# Trial_1_ECE411_Group_15.net
KiCad netlist of a schematic drawn in EAGLE
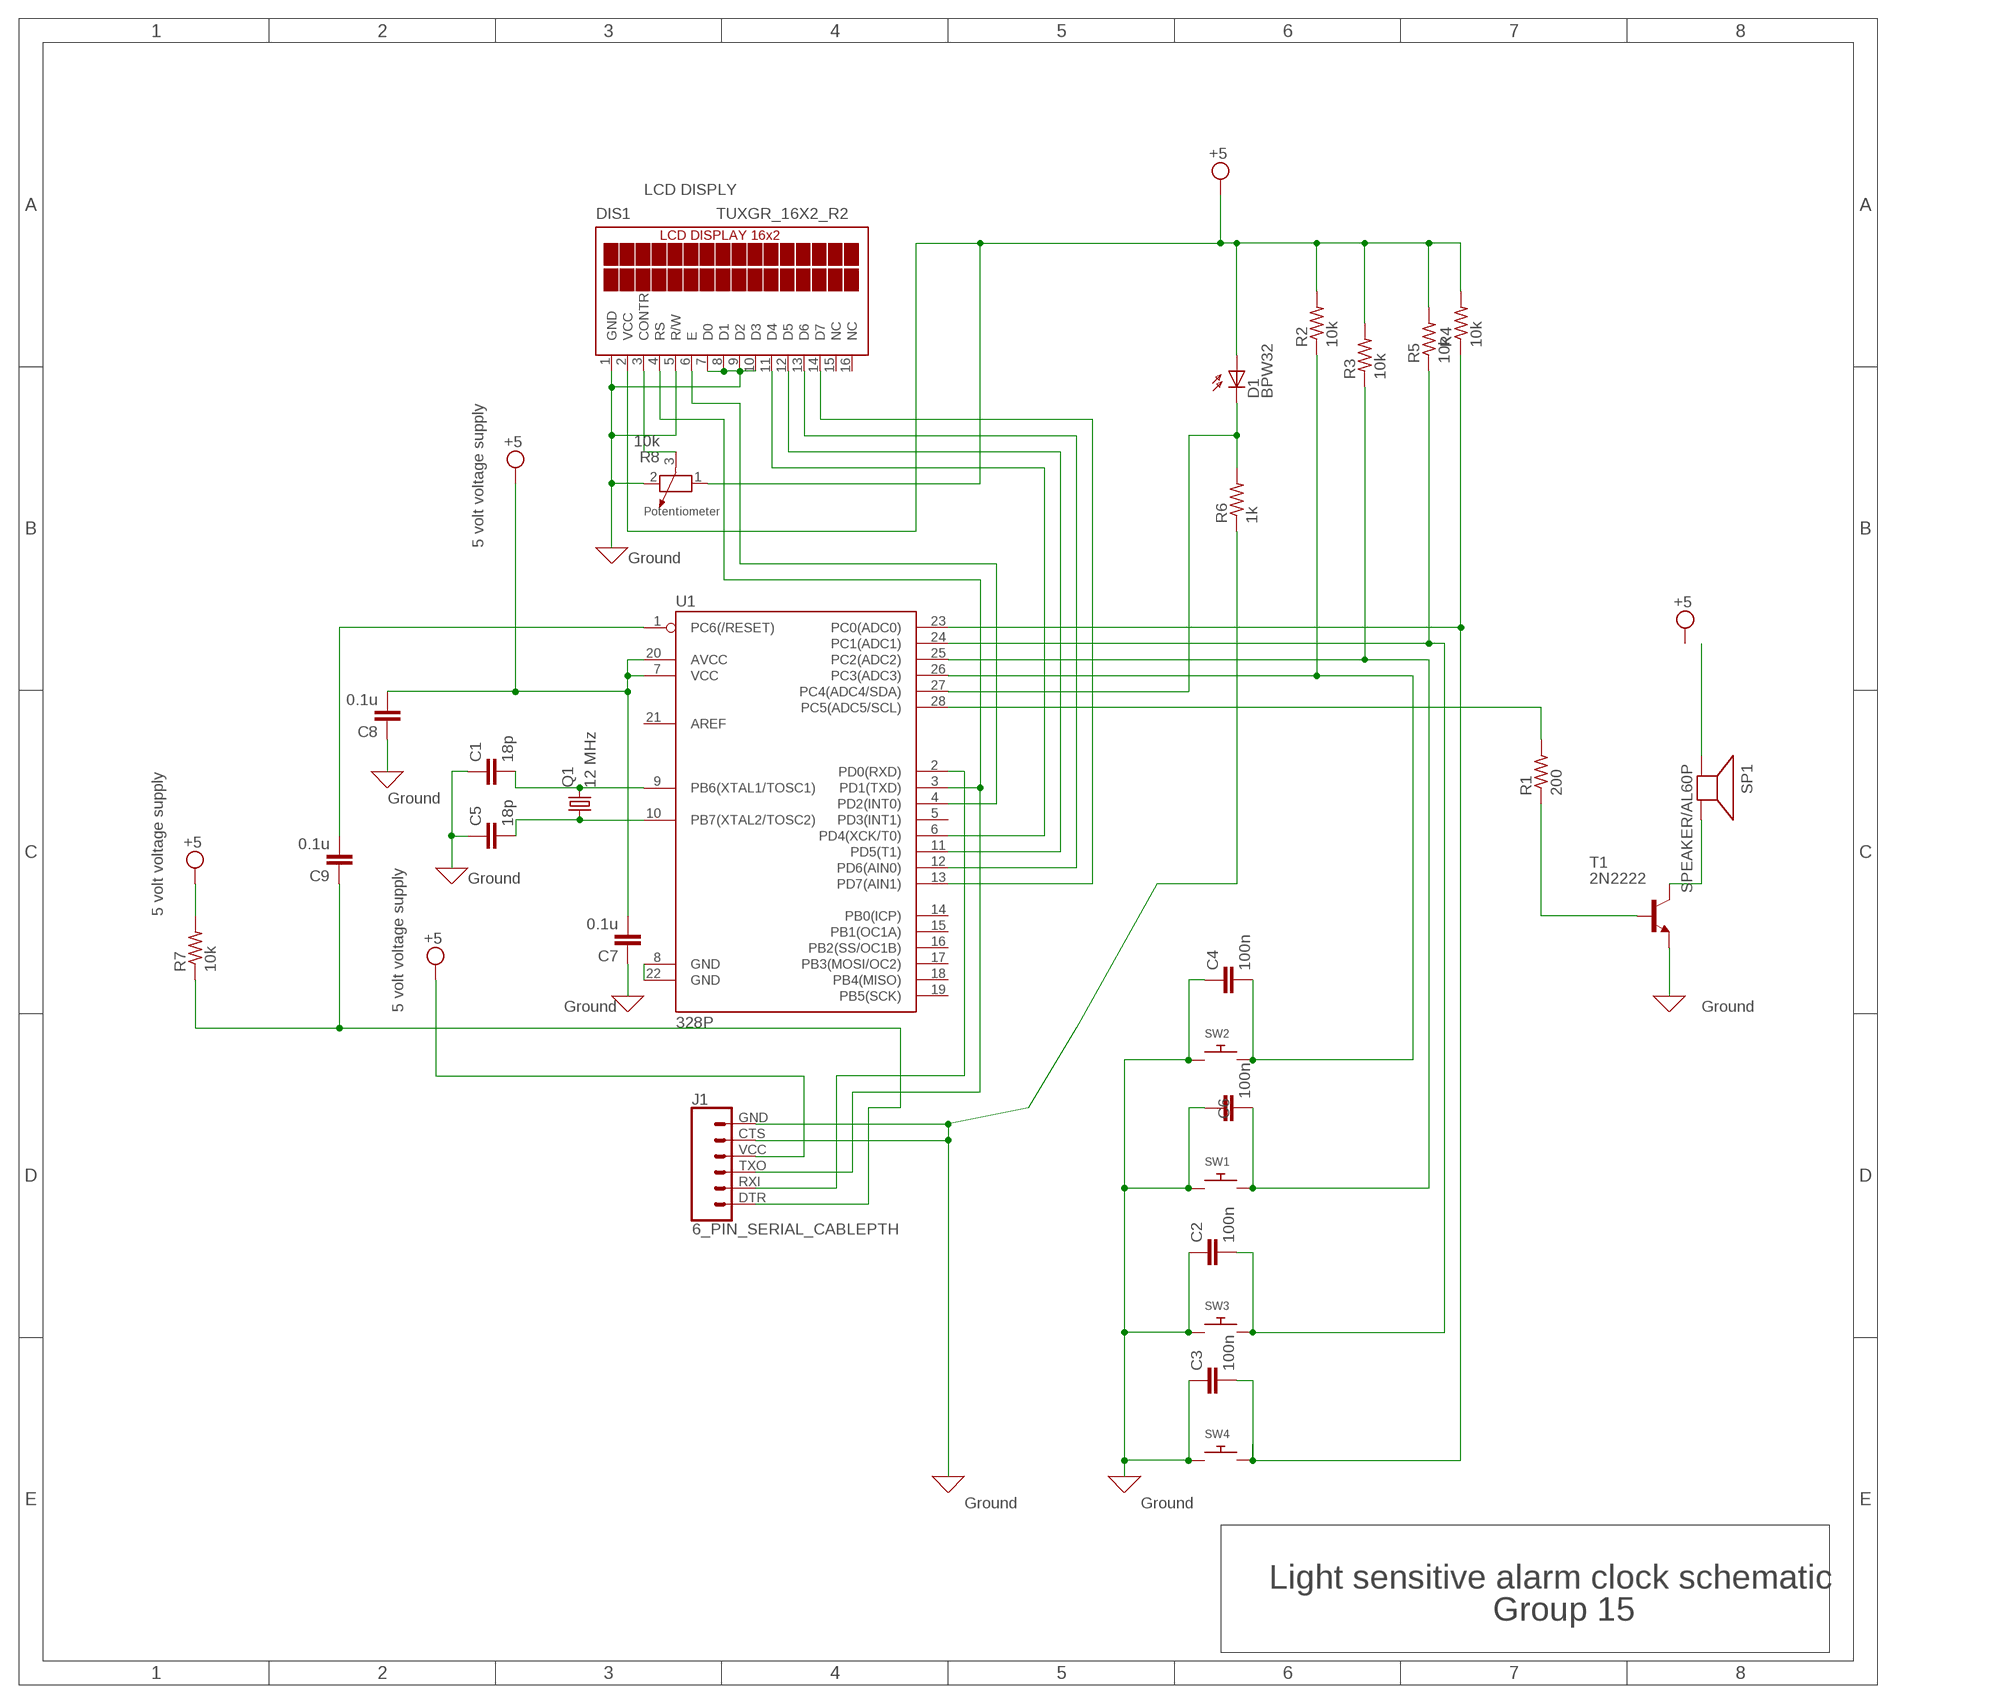
[diagram p0: schematic, sheet 1]

(export (version "E")
  (design (tool "Eeschema 10.0.6"))
  (components
    (comp (ref "C1")
      (value "18p")
      (footprint "eagle-import:C2.5-3")
      (libsource (lib "eagle-import") (part "C2,5-3"))
    )
    (comp (ref "C2")
      (value "100n")
      (footprint "eagle-import:C2.5-3")
      (libsource (lib "eagle-import") (part "C2,5-3"))
    )
    (comp (ref "C3")
      (value "100n")
      (footprint "eagle-import:C2.5-3")
      (libsource (lib "eagle-import") (part "C2,5-3"))
    )
    (comp (ref "C4")
      (value "100n")
      (footprint "eagle-import:C2.5-3")
      (libsource (lib "eagle-import") (part "C2,5-3"))
    )
    (comp (ref "C5")
      (value "18p")
      (footprint "eagle-import:C2.5-3")
      (libsource (lib "eagle-import") (part "C2,5-3"))
    )
    (comp (ref "C6")
      (value "100n")
      (footprint "eagle-import:C2.5-3")
      (libsource (lib "eagle-import") (part "C2,5-3"))
    )
    (comp (ref "C7")
      (value "0.1u")
      (footprint "eagle-import:C2.5-3")
      (libsource (lib "eagle-import") (part "C2,5-3"))
    )
    (comp (ref "C8")
      (value "0.1u")
      (footprint "eagle-import:C2.5-3")
      (libsource (lib "eagle-import") (part "C2,5-3"))
    )
    (comp (ref "C9")
      (value "0.1u")
      (footprint "eagle-import:C2.5-3")
      (libsource (lib "eagle-import") (part "C2,5-3"))
    )
    (comp (ref "D1")
      (value "BPW32")
      (footprint "eagle-import:BPW32")
      (libsource (lib "eagle-import") (part "BPW32"))
    )
    (comp (ref "DIS1")
      (value "TUXGR_16X2_R2")
      (footprint "eagle-import:TUXGR_16X2_R2")
      (libsource (lib "eagle-import") (part "TUXGR_16X2_R2"))
    )
    (comp (ref "J1")
      (value "6_PIN_SERIAL_CABLEPTH")
      (footprint "eagle-import:FTDI_BASIC")
      (libsource (lib "eagle-import") (part "6_PIN_SERIAL_CABLEPTH"))
    )
    (comp (ref "Q1")
      (value "12 MHz")
      (footprint "eagle-import:HC49UP")
      (libsource (lib "eagle-import") (part "CRYSTALHC49UP"))
    )
    (comp (ref "R1")
      (value "200")
      (footprint "eagle-import:0204V")
      (libsource (lib "eagle-import") (part "R-US_0204/2V"))
    )
    (comp (ref "R2")
      (value "10k")
      (footprint "eagle-import:0204V")
      (libsource (lib "eagle-import") (part "R-US_0204/2V"))
    )
    (comp (ref "R3")
      (value "10k")
      (footprint "eagle-import:0204V")
      (libsource (lib "eagle-import") (part "R-US_0204/2V"))
    )
    (comp (ref "R4")
      (value "10k")
      (footprint "eagle-import:0204V")
      (libsource (lib "eagle-import") (part "R-US_0204/2V"))
    )
    (comp (ref "R5")
      (value "10k")
      (footprint "eagle-import:0204V")
      (libsource (lib "eagle-import") (part "R-US_0204/2V"))
    )
    (comp (ref "R6")
      (value "1k")
      (footprint "eagle-import:0204V")
      (libsource (lib "eagle-import") (part "R-US_0204/2V"))
    )
    (comp (ref "R7")
      (value "10k")
      (footprint "eagle-import:0204V")
      (libsource (lib "eagle-import") (part "R-US_0204/2V"))
    )
    (comp (ref "R8")
      (value "10k")
      (footprint "eagle-import:PT-10")
      (libsource (lib "eagle-import") (part "POTENTIOMETER_PT-10"))
    )
    (comp (ref "SP1")
      (value "SPEAKER/AL60P")
      (footprint "eagle-import:AL60P")
      (libsource (lib "eagle-import") (part "SPEAKER/AL60P"))
    )
    (comp (ref "SW1")
      (value "SWITCH_PUSHBUTTONC&K_KSS")
      (footprint "eagle-import:BTN_CK_KSS")
      (libsource (lib "eagle-import") (part "SWITCH_PUSHBUTTONC&K_KSS"))
    )
    (comp (ref "SW2")
      (value "SWITCH_PUSHBUTTONC&K_KSS")
      (footprint "eagle-import:BTN_CK_KSS")
      (libsource (lib "eagle-import") (part "SWITCH_PUSHBUTTONC&K_KSS"))
    )
    (comp (ref "SW3")
      (value "SWITCH_PUSHBUTTONC&K_KSS")
      (footprint "eagle-import:BTN_CK_KSS")
      (libsource (lib "eagle-import") (part "SWITCH_PUSHBUTTONC&K_KSS"))
    )
    (comp (ref "SW4")
      (value "SWITCH_PUSHBUTTONC&K_KSS")
      (footprint "eagle-import:BTN_CK_KSS")
      (libsource (lib "eagle-import") (part "SWITCH_PUSHBUTTONC&K_KSS"))
    )
    (comp (ref "T1")
      (value "2N2222")
      (footprint "eagle-import:TO92-EBC-OVAL")
      (libsource (lib "eagle-import") (part "2N2222"))
    )
    (comp (ref "U1")
      (value "328P")
      (footprint "eagle-import:DIP28")
      (libsource (lib "eagle-import") (part "ATMEGA328P_PDIP"))
    )
  )
  (nets
    (net (code "1") (name "+5") (class "Default")
      (node (ref "C7") (pin "2") (pinfunction "2_2") (pintype "passive"))
      (node (ref "C8") (pin "2") (pinfunction "2_2") (pintype "passive"))
      (node (ref "D1") (pin "A") (pinfunction "A_A") (pintype "passive"))
      (node (ref "DIS1") (pin "2") (pinfunction "VCC_2") (pintype "power_in"))
      (node (ref "J1") (pin "VCC") (pinfunction "4_VCC") (pintype "passive"))
      (node (ref "R2") (pin "2") (pinfunction "2_2") (pintype "passive"))
      (node (ref "R3") (pin "2") (pinfunction "2_2") (pintype "passive"))
      (node (ref "R4") (pin "2") (pinfunction "2_2") (pintype "passive"))
      (node (ref "R5") (pin "2") (pinfunction "2_2") (pintype "passive"))
      (node (ref "R7") (pin "2") (pinfunction "2_2") (pintype "passive"))
      (node (ref "R8") (pin "1") (pinfunction "1_1") (pintype "passive"))
      (node (ref "U1") (pin "20") (pinfunction "AVCC_20") (pintype "bidirectional"))
      (node (ref "U1") (pin "7") (pinfunction "VCC_7") (pintype "bidirectional"))
    )
    (net (code "2") (name "GND") (class "Default")
      (node (ref "C1") (pin "1") (pinfunction "1_1") (pintype "passive"))
      (node (ref "C2") (pin "1") (pinfunction "1_1") (pintype "passive"))
      (node (ref "C3") (pin "1") (pinfunction "1_1") (pintype "passive"))
      (node (ref "C4") (pin "1") (pinfunction "1_1") (pintype "passive"))
      (node (ref "C5") (pin "1") (pinfunction "1_1") (pintype "passive"))
      (node (ref "C6") (pin "1") (pinfunction "1_1") (pintype "passive"))
      (node (ref "C7") (pin "1") (pinfunction "1_1") (pintype "passive"))
      (node (ref "C8") (pin "1") (pinfunction "1_1") (pintype "passive"))
      (node (ref "DIS1") (pin "1") (pinfunction "GND_1") (pintype "power_in"))
      (node (ref "DIS1") (pin "10") (pinfunction "D3_10") (pintype "input"))
      (node (ref "DIS1") (pin "5") (pinfunction "R/W_5") (pintype "input"))
      (node (ref "DIS1") (pin "7") (pinfunction "D0_7") (pintype "input"))
      (node (ref "DIS1") (pin "8") (pinfunction "D1_8") (pintype "input"))
      (node (ref "DIS1") (pin "9") (pinfunction "D2_9") (pintype "input"))
      (node (ref "J1") (pin "CTS") (pinfunction "5_CTS") (pintype "passive"))
      (node (ref "J1") (pin "GND") (pinfunction "6_GND") (pintype "passive"))
      (node (ref "R6") (pin "1") (pinfunction "1_1") (pintype "passive"))
      (node (ref "R8") (pin "2") (pinfunction "2_2") (pintype "passive"))
      (node (ref "SW1") (pin "P$1") (pinfunction "P$1_P$1") (pintype "passive"))
      (node (ref "SW2") (pin "P$1") (pinfunction "P$1_P$1") (pintype "passive"))
      (node (ref "SW3") (pin "P$1") (pinfunction "P$1_P$1") (pintype "passive"))
      (node (ref "SW4") (pin "P$1") (pinfunction "P$1_P$1") (pintype "passive"))
      (node (ref "T1") (pin "E") (pinfunction "E_E") (pintype "passive"))
    )
    (net (code "3") (name "Net-(D1-C)") (class "Default")
      (node (ref "D1") (pin "K") (pinfunction "C_K") (pintype "passive"))
      (node (ref "R6") (pin "2") (pinfunction "2_2") (pintype "passive"))
      (node (ref "U1") (pin "27") (pinfunction "PC4(ADC4/SDA)_27") (pintype "bidirectional"))
    )
    (net (code "4") (name "Net-(DIS1-CONTR)") (class "Default")
      (node (ref "DIS1") (pin "3") (pinfunction "CONTR_3") (pintype "input"))
      (node (ref "R8") (pin "3") (pinfunction "3_3") (pintype "passive"))
    )
    (net (code "5") (name "Net-(DIS1-D4)") (class "Default")
      (node (ref "DIS1") (pin "11") (pinfunction "D4_11") (pintype "input"))
      (node (ref "U1") (pin "6") (pinfunction "PD4(XCK/T0)_6") (pintype "bidirectional"))
    )
    (net (code "6") (name "Net-(DIS1-D5)") (class "Default")
      (node (ref "DIS1") (pin "12") (pinfunction "D5_12") (pintype "input"))
      (node (ref "U1") (pin "11") (pinfunction "PD5(T1)_11") (pintype "bidirectional"))
    )
    (net (code "7") (name "Net-(DIS1-D6)") (class "Default")
      (node (ref "DIS1") (pin "13") (pinfunction "D6_13") (pintype "input"))
      (node (ref "U1") (pin "12") (pinfunction "PD6(AIN0)_12") (pintype "bidirectional"))
    )
    (net (code "8") (name "Net-(DIS1-D7)") (class "Default")
      (node (ref "DIS1") (pin "14") (pinfunction "D7_14") (pintype "input"))
      (node (ref "U1") (pin "13") (pinfunction "PD7(AIN1)_13") (pintype "bidirectional"))
    )
    (net (code "9") (name "Net-(DIS1-E)") (class "Default")
      (node (ref "DIS1") (pin "6") (pinfunction "E_6") (pintype "input"))
      (node (ref "U1") (pin "4") (pinfunction "PD2(INT0)_4") (pintype "bidirectional"))
    )
    (net (code "10") (name "Net-(DIS1-RS)") (class "Default")
      (node (ref "DIS1") (pin "4") (pinfunction "RS_4") (pintype "input"))
      (node (ref "J1") (pin "TXO") (pinfunction "3_TXO") (pintype "passive"))
      (node (ref "U1") (pin "3") (pinfunction "PD1(TXD)_3") (pintype "bidirectional"))
    )
    (net (code "11") (name "Net-(J1-1)") (class "Default")
      (node (ref "C9") (pin "1") (pinfunction "1_1") (pintype "passive"))
      (node (ref "J1") (pin "DTR") (pinfunction "1_DTR") (pintype "passive"))
      (node (ref "R7") (pin "1") (pinfunction "1_1") (pintype "passive"))
    )
    (net (code "12") (name "Net-(J1-2)") (class "Default")
      (node (ref "J1") (pin "RXI") (pinfunction "2_RXI") (pintype "passive"))
      (node (ref "U1") (pin "2") (pinfunction "PD0(RXD)_2") (pintype "bidirectional"))
    )
    (net (code "13") (name "Net-(R1-Pad1)") (class "Default")
      (node (ref "R1") (pin "1") (pinfunction "1_1") (pintype "passive"))
      (node (ref "T1") (pin "B") (pinfunction "B_B") (pintype "passive"))
    )
    (net (code "14") (name "Net-(SP1--)") (class "Default")
      (node (ref "SP1") (pin "2") (pinfunction "-_2") (pintype "passive"))
      (node (ref "T1") (pin "C") (pinfunction "C_C") (pintype "passive"))
    )
    (net (code "15") (name "Net-(U1-GND-Pad22)") (class "Default")
      (node (ref "U1") (pin "22") (pinfunction "GND_22") (pintype "bidirectional"))
      (node (ref "U1") (pin "8") (pinfunction "GND_8") (pintype "bidirectional"))
    )
    (net (code "16") (name "Net-(U1-PB6(XTAL1{slash}TOSC1))") (class "Default")
      (node (ref "C1") (pin "2") (pinfunction "2_2") (pintype "passive"))
      (node (ref "Q1") (pin "2") (pinfunction "2_2") (pintype "passive"))
      (node (ref "U1") (pin "9") (pinfunction "PB6(XTAL1/TOSC1)_9") (pintype "bidirectional"))
    )
    (net (code "17") (name "Net-(U1-PB7(XTAL2{slash}TOSC2))") (class "Default")
      (node (ref "C5") (pin "2") (pinfunction "2_2") (pintype "passive"))
      (node (ref "Q1") (pin "1") (pinfunction "1_1") (pintype "passive"))
      (node (ref "U1") (pin "10") (pinfunction "PB7(XTAL2/TOSC2)_10") (pintype "bidirectional"))
    )
    (net (code "18") (name "Net-(U1-PC0(ADC0))") (class "Default")
      (node (ref "C3") (pin "2") (pinfunction "2_2") (pintype "passive"))
      (node (ref "R4") (pin "1") (pinfunction "1_1") (pintype "passive"))
      (node (ref "SW4") (pin "P$2") (pinfunction "P$2_P$2") (pintype "passive"))
      (node (ref "U1") (pin "23") (pinfunction "PC0(ADC0)_23") (pintype "bidirectional"))
    )
    (net (code "19") (name "Net-(U1-PC1(ADC1))") (class "Default")
      (node (ref "C2") (pin "2") (pinfunction "2_2") (pintype "passive"))
      (node (ref "R5") (pin "1") (pinfunction "1_1") (pintype "passive"))
      (node (ref "SW3") (pin "P$2") (pinfunction "P$2_P$2") (pintype "passive"))
      (node (ref "U1") (pin "24") (pinfunction "PC1(ADC1)_24") (pintype "bidirectional"))
    )
    (net (code "20") (name "Net-(U1-PC2(ADC2))") (class "Default")
      (node (ref "C6") (pin "2") (pinfunction "2_2") (pintype "passive"))
      (node (ref "R3") (pin "1") (pinfunction "1_1") (pintype "passive"))
      (node (ref "SW1") (pin "P$2") (pinfunction "P$2_P$2") (pintype "passive"))
      (node (ref "U1") (pin "25") (pinfunction "PC2(ADC2)_25") (pintype "bidirectional"))
    )
    (net (code "21") (name "Net-(U1-PC3(ADC3))") (class "Default")
      (node (ref "C4") (pin "2") (pinfunction "2_2") (pintype "passive"))
      (node (ref "R2") (pin "1") (pinfunction "1_1") (pintype "passive"))
      (node (ref "SW2") (pin "P$2") (pinfunction "P$2_P$2") (pintype "passive"))
      (node (ref "U1") (pin "26") (pinfunction "PC3(ADC3)_26") (pintype "bidirectional"))
    )
    (net (code "22") (name "Net-(U1-PC5(ADC5{slash}SCL))") (class "Default")
      (node (ref "R1") (pin "2") (pinfunction "2_2") (pintype "passive"))
      (node (ref "U1") (pin "28") (pinfunction "PC5(ADC5/SCL)_28") (pintype "bidirectional"))
    )
    (net (code "23") (name "Net-(U1-PC6({slash}RESET))") (class "Default")
      (node (ref "C9") (pin "2") (pinfunction "2_2") (pintype "passive"))
      (node (ref "U1") (pin "1") (pinfunction "PC6(/RESET)_1") (pintype "bidirectional"))
    )
    (net (code "24") (name "unconnected-(DIS1-NC-Pad15)") (class "Default")
      (node (ref "DIS1") (pin "15") (pinfunction "NC_15") (pintype "no_connect"))
    )
    (net (code "25") (name "unconnected-(DIS1-NC-Pad16)") (class "Default")
      (node (ref "DIS1") (pin "16") (pinfunction "NC_16") (pintype "no_connect"))
    )
    (net (code "26") (name "unconnected-(SP1-+-Pad1)") (class "Default")
      (node (ref "SP1") (pin "1") (pinfunction "+_1") (pintype "passive"))
    )
    (net (code "27") (name "unconnected-(U1-AREF-Pad21)") (class "Default")
      (node (ref "U1") (pin "21") (pinfunction "AREF_21") (pintype "bidirectional"))
    )
    (net (code "28") (name "unconnected-(U1-PB0(ICP)-Pad14)") (class "Default")
      (node (ref "U1") (pin "14") (pinfunction "PB0(ICP)_14") (pintype "bidirectional"))
    )
    (net (code "29") (name "unconnected-(U1-PB1(OC1A)-Pad15)") (class "Default")
      (node (ref "U1") (pin "15") (pinfunction "PB1(OC1A)_15") (pintype "bidirectional"))
    )
    (net (code "30") (name "unconnected-(U1-PB2(SS{slash}OC1B)-Pad16)") (class "Default")
      (node (ref "U1") (pin "16") (pinfunction "PB2(SS/OC1B)_16") (pintype "bidirectional"))
    )
    (net (code "31") (name "unconnected-(U1-PB3(MOSI{slash}OC2)-Pad17)") (class "Default")
      (node (ref "U1") (pin "17") (pinfunction "PB3(MOSI/OC2)_17") (pintype "bidirectional"))
    )
    (net (code "32") (name "unconnected-(U1-PB4(MISO)-Pad18)") (class "Default")
      (node (ref "U1") (pin "18") (pinfunction "PB4(MISO)_18") (pintype "bidirectional"))
    )
    (net (code "33") (name "unconnected-(U1-PB5(SCK)-Pad19)") (class "Default")
      (node (ref "U1") (pin "19") (pinfunction "PB5(SCK)_19") (pintype "bidirectional"))
    )
    (net (code "34") (name "unconnected-(U1-PD3(INT1)-Pad5)") (class "Default")
      (node (ref "U1") (pin "5") (pinfunction "PD3(INT1)_5") (pintype "bidirectional"))
    )
  )
)
